# pcb1d.net
KiCad netlist of a schematic drawn in EAGLE
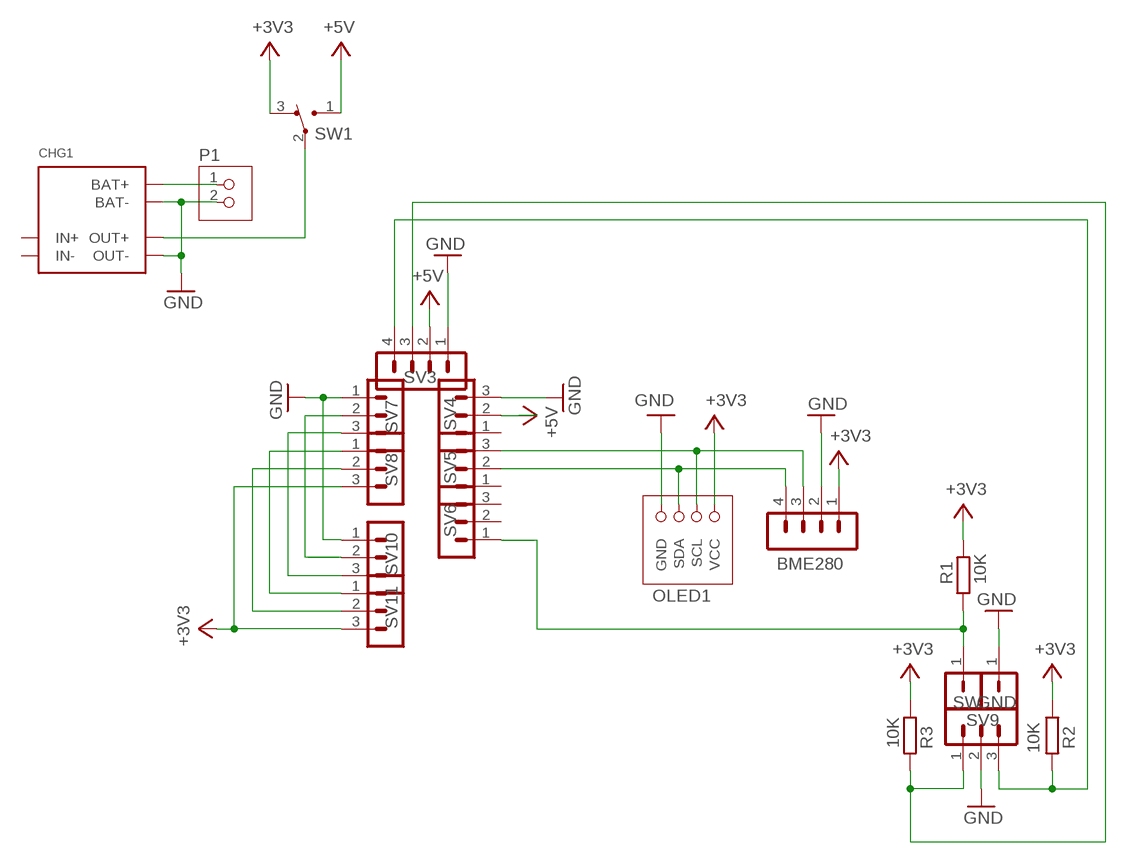
[diagram p0: schematic, sheet 1]

(export (version "E")
  (design (tool "Eeschema 10.0.6"))
  (components
    (comp (ref "BME280")
      (value "PINHEAD-MA04-1")
      (footprint "eagle-import:PINHEAD-MA04-1")
      (libsource (lib "eagle-import") (part "PINHEAD-MA04-1"))
    )
    (comp (ref "CHG1")
      (value "TP4056MOD2-TYPE-C")
      (footprint "eagle-import:TP4056MOD2-TYPE-C")
      (libsource (lib "eagle-import") (part "TP4056MOD2-TYPE-C"))
    )
    (comp (ref "GND")
      (value "PINHEAD-MA01-1")
      (footprint "eagle-import:PINHEAD-MA01-1")
      (libsource (lib "eagle-import") (part "PINHEAD-MA01-1"))
    )
    (comp (ref "OLED1")
      (value "OLED-SSD1306-0.96")
      (footprint "eagle-import:OLED-I2C-0.96")
      (libsource (lib "eagle-import") (part "OLED-SSD1306-0.96"))
    )
    (comp (ref "P1")
      (value "JST-PH2")
      (footprint "eagle-import:JST-PH2")
      (libsource (lib "eagle-import") (part "JST-PH2"))
    )
    (comp (ref "R1")
      (value "10K")
      (footprint "eagle-import:0204_5")
      (libsource (lib "eagle-import") (part "R-EU_0204/5"))
    )
    (comp (ref "R2")
      (value "10K")
      (footprint "eagle-import:0204_5")
      (libsource (lib "eagle-import") (part "R-EU_0204/5"))
    )
    (comp (ref "R3")
      (value "10K")
      (footprint "eagle-import:0204_5")
      (libsource (lib "eagle-import") (part "R-EU_0204/5"))
    )
    (comp (ref "SV3")
      (value "PINHEAD-MA04-1")
      (footprint "eagle-import:PINHEAD-MA04-1")
      (libsource (lib "eagle-import") (part "PINHEAD-MA04-1"))
    )
    (comp (ref "SV4")
      (value "PINHEAD-MA03-1")
      (footprint "eagle-import:PINHEAD-MA03-1")
      (libsource (lib "eagle-import") (part "PINHEAD-MA03-1"))
    )
    (comp (ref "SV5")
      (value "PINHEAD-MA03-1")
      (footprint "eagle-import:PINHEAD-MA03-1")
      (libsource (lib "eagle-import") (part "PINHEAD-MA03-1"))
    )
    (comp (ref "SV6")
      (value "PINHEAD-MA03-1")
      (footprint "eagle-import:PINHEAD-MA03-1")
      (libsource (lib "eagle-import") (part "PINHEAD-MA03-1"))
    )
    (comp (ref "SV7")
      (value "PINHEAD-MA03-1")
      (footprint "eagle-import:PINHEAD-MA03-1")
      (libsource (lib "eagle-import") (part "PINHEAD-MA03-1"))
    )
    (comp (ref "SV8")
      (value "PINHEAD-MA03-1")
      (footprint "eagle-import:PINHEAD-MA03-1")
      (libsource (lib "eagle-import") (part "PINHEAD-MA03-1"))
    )
    (comp (ref "SV9")
      (value "PINHEAD-MA03-1")
      (footprint "eagle-import:PINHEAD-MA03-1")
      (libsource (lib "eagle-import") (part "PINHEAD-MA03-1"))
    )
    (comp (ref "SV10")
      (value "PINHEAD-MA03-1")
      (footprint "eagle-import:PINHEAD-MA03-1")
      (libsource (lib "eagle-import") (part "PINHEAD-MA03-1"))
    )
    (comp (ref "SV11")
      (value "PINHEAD-MA03-1")
      (footprint "eagle-import:PINHEAD-MA03-1")
      (libsource (lib "eagle-import") (part "PINHEAD-MA03-1"))
    )
    (comp (ref "SW")
      (value "PINHEAD-MA01-1")
      (footprint "eagle-import:PINHEAD-MA01-1")
      (libsource (lib "eagle-import") (part "PINHEAD-MA01-1"))
    )
    (comp (ref "SW1")
      (value "SW3-1")
      (footprint "eagle-import:SW3-1")
      (fields (field (name "MF") "HiLetgo"))
      (libsource (lib "eagle-import") (part "SW3-1"))
    )
  )
  (nets
    (net (code "1") (name "+3V3") (class "Default")
      (node (ref "BME280") (pin "1") (pinfunction "1_1") (pintype "passive"))
      (node (ref "OLED1") (pin "VCC") (pinfunction "VCC_VCC") (pintype "bidirectional"))
      (node (ref "R1") (pin "2") (pinfunction "2_2") (pintype "passive"))
      (node (ref "R2") (pin "1") (pinfunction "1_1") (pintype "passive"))
      (node (ref "R3") (pin "1") (pinfunction "1_1") (pintype "passive"))
      (node (ref "SV11") (pin "3") (pinfunction "3_3") (pintype "passive"))
      (node (ref "SV8") (pin "3") (pinfunction "3_3") (pintype "passive"))
      (node (ref "SW1") (pin "3") (pinfunction "3_3") (pintype "passive"))
    )
    (net (code "2") (name "+5V") (class "Default")
      (node (ref "SV3") (pin "2") (pinfunction "2_2") (pintype "passive"))
      (node (ref "SV4") (pin "2") (pinfunction "2_2") (pintype "passive"))
      (node (ref "SW1") (pin "1") (pinfunction "1_1") (pintype "passive"))
    )
    (net (code "3") (name "GND") (class "Default")
      (node (ref "BME280") (pin "2") (pinfunction "2_2") (pintype "passive"))
      (node (ref "CHG1") (pin "BAT-") (pinfunction "BAT-_BAT-") (pintype "passive"))
      (node (ref "CHG1") (pin "OUT-") (pinfunction "OUT-_OUT-") (pintype "passive"))
      (node (ref "GND") (pin "1") (pinfunction "1_1") (pintype "passive"))
      (node (ref "OLED1") (pin "GND") (pinfunction "GND_GND") (pintype "bidirectional"))
      (node (ref "P1") (pin "2") (pinfunction "2_2") (pintype "passive"))
      (node (ref "SV10") (pin "1") (pinfunction "1_1") (pintype "passive"))
      (node (ref "SV3") (pin "1") (pinfunction "1_1") (pintype "passive"))
      (node (ref "SV4") (pin "3") (pinfunction "3_3") (pintype "passive"))
      (node (ref "SV7") (pin "1") (pinfunction "1_1") (pintype "passive"))
      (node (ref "SV9") (pin "2") (pinfunction "2_2") (pintype "passive"))
    )
    (net (code "4") (name "Net-(BME280-Pad3)") (class "Default")
      (node (ref "BME280") (pin "3") (pinfunction "3_3") (pintype "passive"))
      (node (ref "OLED1") (pin "SCL") (pinfunction "SCL_SCL") (pintype "bidirectional"))
      (node (ref "SV5") (pin "3") (pinfunction "3_3") (pintype "passive"))
    )
    (net (code "5") (name "Net-(BME280-Pad4)") (class "Default")
      (node (ref "BME280") (pin "4") (pinfunction "4_4") (pintype "passive"))
      (node (ref "OLED1") (pin "SDA") (pinfunction "SDA_SDA") (pintype "bidirectional"))
      (node (ref "SV5") (pin "2") (pinfunction "2_2") (pintype "passive"))
    )
    (net (code "6") (name "Net-(CHG1-PadBAT+)") (class "Default")
      (node (ref "CHG1") (pin "BAT+") (pinfunction "BAT+_BAT+") (pintype "passive"))
      (node (ref "P1") (pin "1") (pinfunction "1_1") (pintype "passive"))
    )
    (net (code "7") (name "Net-(CHG1-PadOUT+)") (class "Default")
      (node (ref "CHG1") (pin "OUT+") (pinfunction "OUT+_OUT+") (pintype "passive"))
      (node (ref "SW1") (pin "2") (pinfunction "2_2") (pintype "passive"))
    )
    (net (code "8") (name "Net-(R1-Pad1)") (class "Default")
      (node (ref "R1") (pin "1") (pinfunction "1_1") (pintype "passive"))
      (node (ref "SV6") (pin "1") (pinfunction "1_1") (pintype "passive"))
      (node (ref "SW") (pin "1") (pinfunction "1_1") (pintype "passive"))
    )
    (net (code "9") (name "Net-(R2-Pad2)") (class "Default")
      (node (ref "R2") (pin "2") (pinfunction "2_2") (pintype "passive"))
      (node (ref "SV3") (pin "4") (pinfunction "4_4") (pintype "passive"))
      (node (ref "SV9") (pin "3") (pinfunction "3_3") (pintype "passive"))
    )
    (net (code "10") (name "Net-(R3-Pad2)") (class "Default")
      (node (ref "R3") (pin "2") (pinfunction "2_2") (pintype "passive"))
      (node (ref "SV3") (pin "3") (pinfunction "3_3") (pintype "passive"))
      (node (ref "SV9") (pin "1") (pinfunction "1_1") (pintype "passive"))
    )
    (net (code "11") (name "Net-(SV10-Pad2)") (class "Default")
      (node (ref "SV10") (pin "2") (pinfunction "2_2") (pintype "passive"))
      (node (ref "SV7") (pin "2") (pinfunction "2_2") (pintype "passive"))
    )
    (net (code "12") (name "Net-(SV10-Pad3)") (class "Default")
      (node (ref "SV10") (pin "3") (pinfunction "3_3") (pintype "passive"))
      (node (ref "SV7") (pin "3") (pinfunction "3_3") (pintype "passive"))
    )
    (net (code "13") (name "Net-(SV11-Pad1)") (class "Default")
      (node (ref "SV11") (pin "1") (pinfunction "1_1") (pintype "passive"))
      (node (ref "SV8") (pin "1") (pinfunction "1_1") (pintype "passive"))
    )
    (net (code "14") (name "Net-(SV11-Pad2)") (class "Default")
      (node (ref "SV11") (pin "2") (pinfunction "2_2") (pintype "passive"))
      (node (ref "SV8") (pin "2") (pinfunction "2_2") (pintype "passive"))
    )
    (net (code "15") (name "unconnected-(CHG1-PadIN+)") (class "Default")
      (node (ref "CHG1") (pin "IN+") (pinfunction "IN+_IN+") (pintype "passive"))
    )
    (net (code "16") (name "unconnected-(CHG1-PadIN-)") (class "Default")
      (node (ref "CHG1") (pin "IN-") (pinfunction "IN-_IN-") (pintype "passive"))
    )
    (net (code "17") (name "unconnected-(SV4-Pad1)") (class "Default")
      (node (ref "SV4") (pin "1") (pinfunction "1_1") (pintype "passive"))
    )
    (net (code "18") (name "unconnected-(SV5-Pad1)") (class "Default")
      (node (ref "SV5") (pin "1") (pinfunction "1_1") (pintype "passive"))
    )
    (net (code "19") (name "unconnected-(SV6-Pad2)") (class "Default")
      (node (ref "SV6") (pin "2") (pinfunction "2_2") (pintype "passive"))
    )
    (net (code "20") (name "unconnected-(SV6-Pad3)") (class "Default")
      (node (ref "SV6") (pin "3") (pinfunction "3_3") (pintype "passive"))
    )
  )
)
